# Facee.net
KiCad netlist of a schematic drawn in EAGLE
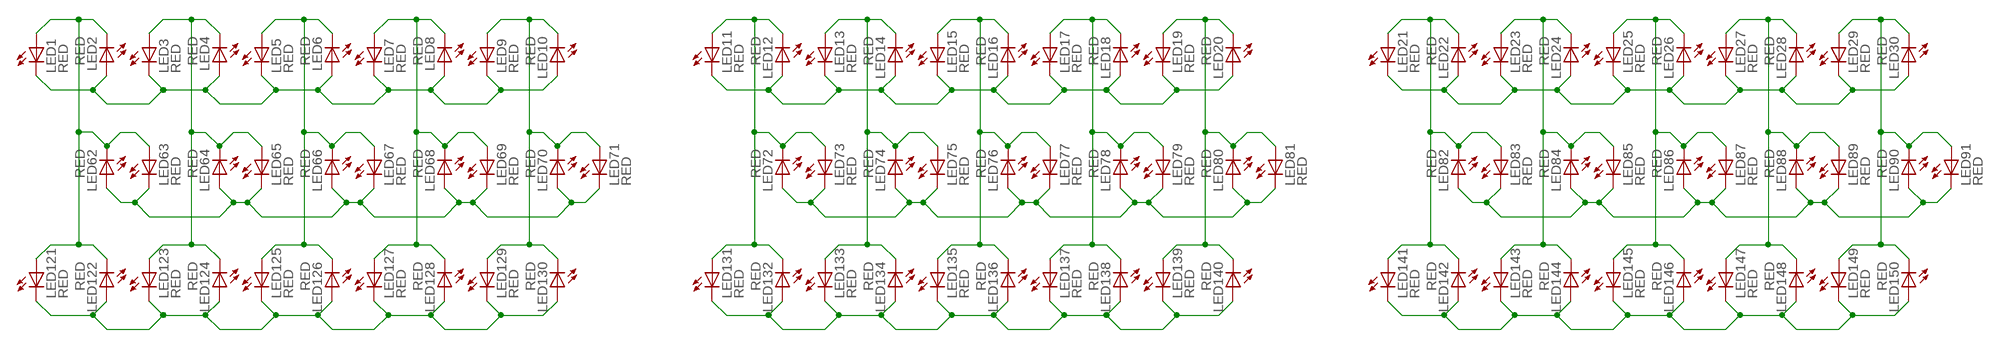
[diagram p0: schematic, sheet 1, part 1 of 2]
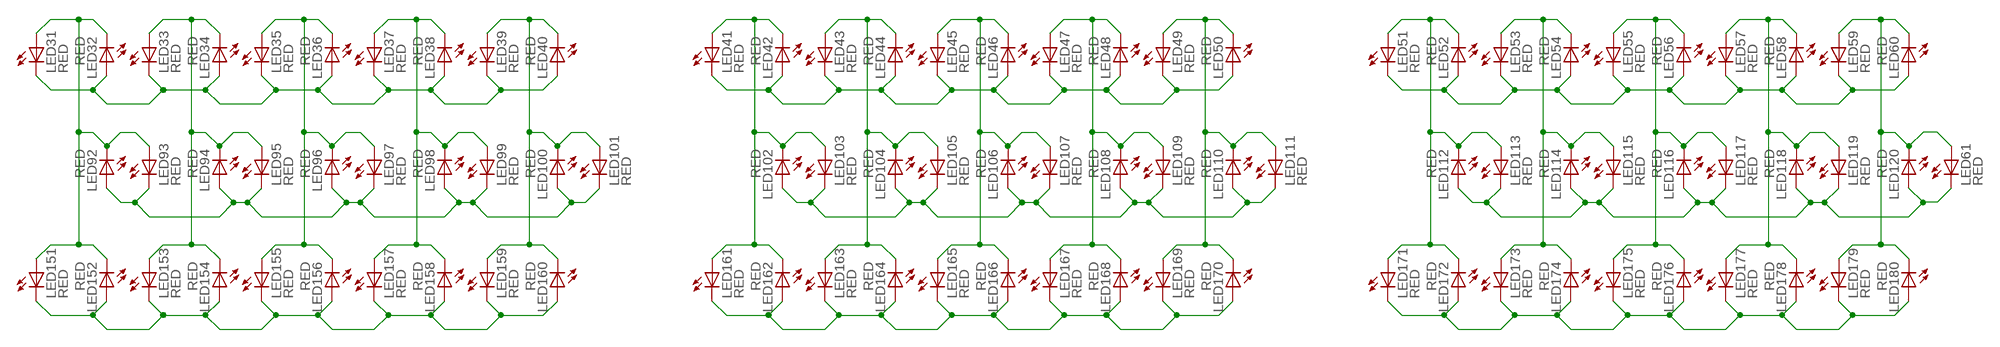
[diagram p1: schematic, sheet 1, part 2 of 2]

(export (version "E")
  (design (tool "Eeschema 10.0.6"))
  (components
    (comp (ref "LED1")
      (value "RED")
      (footprint "eagle-import:LED-0603")
      (libsource (lib "eagle-import") (part "LED0603"))
    )
    (comp (ref "LED2")
      (value "RED")
      (footprint "eagle-import:LED-0603")
      (libsource (lib "eagle-import") (part "LED0603"))
    )
    (comp (ref "LED3")
      (value "RED")
      (footprint "eagle-import:LED-0603")
      (libsource (lib "eagle-import") (part "LED0603"))
    )
    (comp (ref "LED4")
      (value "RED")
      (footprint "eagle-import:LED-0603")
      (libsource (lib "eagle-import") (part "LED0603"))
    )
    (comp (ref "LED5")
      (value "RED")
      (footprint "eagle-import:LED-0603")
      (libsource (lib "eagle-import") (part "LED0603"))
    )
    (comp (ref "LED6")
      (value "RED")
      (footprint "eagle-import:LED-0603")
      (libsource (lib "eagle-import") (part "LED0603"))
    )
    (comp (ref "LED7")
      (value "RED")
      (footprint "eagle-import:LED-0603")
      (libsource (lib "eagle-import") (part "LED0603"))
    )
    (comp (ref "LED8")
      (value "RED")
      (footprint "eagle-import:LED-0603")
      (libsource (lib "eagle-import") (part "LED0603"))
    )
    (comp (ref "LED9")
      (value "RED")
      (footprint "eagle-import:LED-0603")
      (libsource (lib "eagle-import") (part "LED0603"))
    )
    (comp (ref "LED10")
      (value "RED")
      (footprint "eagle-import:LED-0603")
      (libsource (lib "eagle-import") (part "LED0603"))
    )
    (comp (ref "LED11")
      (value "RED")
      (footprint "eagle-import:LED-0603")
      (libsource (lib "eagle-import") (part "LED0603"))
    )
    (comp (ref "LED12")
      (value "RED")
      (footprint "eagle-import:LED-0603")
      (libsource (lib "eagle-import") (part "LED0603"))
    )
    (comp (ref "LED13")
      (value "RED")
      (footprint "eagle-import:LED-0603")
      (libsource (lib "eagle-import") (part "LED0603"))
    )
    (comp (ref "LED14")
      (value "RED")
      (footprint "eagle-import:LED-0603")
      (libsource (lib "eagle-import") (part "LED0603"))
    )
    (comp (ref "LED15")
      (value "RED")
      (footprint "eagle-import:LED-0603")
      (libsource (lib "eagle-import") (part "LED0603"))
    )
    (comp (ref "LED16")
      (value "RED")
      (footprint "eagle-import:LED-0603")
      (libsource (lib "eagle-import") (part "LED0603"))
    )
    (comp (ref "LED17")
      (value "RED")
      (footprint "eagle-import:LED-0603")
      (libsource (lib "eagle-import") (part "LED0603"))
    )
    (comp (ref "LED18")
      (value "RED")
      (footprint "eagle-import:LED-0603")
      (libsource (lib "eagle-import") (part "LED0603"))
    )
    (comp (ref "LED19")
      (value "RED")
      (footprint "eagle-import:LED-0603")
      (libsource (lib "eagle-import") (part "LED0603"))
    )
    (comp (ref "LED20")
      (value "RED")
      (footprint "eagle-import:LED-0603")
      (libsource (lib "eagle-import") (part "LED0603"))
    )
    (comp (ref "LED21")
      (value "RED")
      (footprint "eagle-import:LED-0603")
      (libsource (lib "eagle-import") (part "LED0603"))
    )
    (comp (ref "LED22")
      (value "RED")
      (footprint "eagle-import:LED-0603")
      (libsource (lib "eagle-import") (part "LED0603"))
    )
    (comp (ref "LED23")
      (value "RED")
      (footprint "eagle-import:LED-0603")
      (libsource (lib "eagle-import") (part "LED0603"))
    )
    (comp (ref "LED24")
      (value "RED")
      (footprint "eagle-import:LED-0603")
      (libsource (lib "eagle-import") (part "LED0603"))
    )
    (comp (ref "LED25")
      (value "RED")
      (footprint "eagle-import:LED-0603")
      (libsource (lib "eagle-import") (part "LED0603"))
    )
    (comp (ref "LED26")
      (value "RED")
      (footprint "eagle-import:LED-0603")
      (libsource (lib "eagle-import") (part "LED0603"))
    )
    (comp (ref "LED27")
      (value "RED")
      (footprint "eagle-import:LED-0603")
      (libsource (lib "eagle-import") (part "LED0603"))
    )
    (comp (ref "LED28")
      (value "RED")
      (footprint "eagle-import:LED-0603")
      (libsource (lib "eagle-import") (part "LED0603"))
    )
    (comp (ref "LED29")
      (value "RED")
      (footprint "eagle-import:LED-0603")
      (libsource (lib "eagle-import") (part "LED0603"))
    )
    (comp (ref "LED30")
      (value "RED")
      (footprint "eagle-import:LED-0603")
      (libsource (lib "eagle-import") (part "LED0603"))
    )
    (comp (ref "LED31")
      (value "RED")
      (footprint "eagle-import:LED-0603")
      (libsource (lib "eagle-import") (part "LED0603"))
    )
    (comp (ref "LED32")
      (value "RED")
      (footprint "eagle-import:LED-0603")
      (libsource (lib "eagle-import") (part "LED0603"))
    )
    (comp (ref "LED33")
      (value "RED")
      (footprint "eagle-import:LED-0603")
      (libsource (lib "eagle-import") (part "LED0603"))
    )
    (comp (ref "LED34")
      (value "RED")
      (footprint "eagle-import:LED-0603")
      (libsource (lib "eagle-import") (part "LED0603"))
    )
    (comp (ref "LED35")
      (value "RED")
      (footprint "eagle-import:LED-0603")
      (libsource (lib "eagle-import") (part "LED0603"))
    )
    (comp (ref "LED36")
      (value "RED")
      (footprint "eagle-import:LED-0603")
      (libsource (lib "eagle-import") (part "LED0603"))
    )
    (comp (ref "LED37")
      (value "RED")
      (footprint "eagle-import:LED-0603")
      (libsource (lib "eagle-import") (part "LED0603"))
    )
    (comp (ref "LED38")
      (value "RED")
      (footprint "eagle-import:LED-0603")
      (libsource (lib "eagle-import") (part "LED0603"))
    )
    (comp (ref "LED39")
      (value "RED")
      (footprint "eagle-import:LED-0603")
      (libsource (lib "eagle-import") (part "LED0603"))
    )
    (comp (ref "LED40")
      (value "RED")
      (footprint "eagle-import:LED-0603")
      (libsource (lib "eagle-import") (part "LED0603"))
    )
    (comp (ref "LED41")
      (value "RED")
      (footprint "eagle-import:LED-0603")
      (libsource (lib "eagle-import") (part "LED0603"))
    )
    (comp (ref "LED42")
      (value "RED")
      (footprint "eagle-import:LED-0603")
      (libsource (lib "eagle-import") (part "LED0603"))
    )
    (comp (ref "LED43")
      (value "RED")
      (footprint "eagle-import:LED-0603")
      (libsource (lib "eagle-import") (part "LED0603"))
    )
    (comp (ref "LED44")
      (value "RED")
      (footprint "eagle-import:LED-0603")
      (libsource (lib "eagle-import") (part "LED0603"))
    )
    (comp (ref "LED45")
      (value "RED")
      (footprint "eagle-import:LED-0603")
      (libsource (lib "eagle-import") (part "LED0603"))
    )
    (comp (ref "LED46")
      (value "RED")
      (footprint "eagle-import:LED-0603")
      (libsource (lib "eagle-import") (part "LED0603"))
    )
    (comp (ref "LED47")
      (value "RED")
      (footprint "eagle-import:LED-0603")
      (libsource (lib "eagle-import") (part "LED0603"))
    )
    (comp (ref "LED48")
      (value "RED")
      (footprint "eagle-import:LED-0603")
      (libsource (lib "eagle-import") (part "LED0603"))
    )
    (comp (ref "LED49")
      (value "RED")
      (footprint "eagle-import:LED-0603")
      (libsource (lib "eagle-import") (part "LED0603"))
    )
    (comp (ref "LED50")
      (value "RED")
      (footprint "eagle-import:LED-0603")
      (libsource (lib "eagle-import") (part "LED0603"))
    )
    (comp (ref "LED51")
      (value "RED")
      (footprint "eagle-import:LED-0603")
      (libsource (lib "eagle-import") (part "LED0603"))
    )
    (comp (ref "LED52")
      (value "RED")
      (footprint "eagle-import:LED-0603")
      (libsource (lib "eagle-import") (part "LED0603"))
    )
    (comp (ref "LED53")
      (value "RED")
      (footprint "eagle-import:LED-0603")
      (libsource (lib "eagle-import") (part "LED0603"))
    )
    (comp (ref "LED54")
      (value "RED")
      (footprint "eagle-import:LED-0603")
      (libsource (lib "eagle-import") (part "LED0603"))
    )
    (comp (ref "LED55")
      (value "RED")
      (footprint "eagle-import:LED-0603")
      (libsource (lib "eagle-import") (part "LED0603"))
    )
    (comp (ref "LED56")
      (value "RED")
      (footprint "eagle-import:LED-0603")
      (libsource (lib "eagle-import") (part "LED0603"))
    )
    (comp (ref "LED57")
      (value "RED")
      (footprint "eagle-import:LED-0603")
      (libsource (lib "eagle-import") (part "LED0603"))
    )
    (comp (ref "LED58")
      (value "RED")
      (footprint "eagle-import:LED-0603")
      (libsource (lib "eagle-import") (part "LED0603"))
    )
    (comp (ref "LED59")
      (value "RED")
      (footprint "eagle-import:LED-0603")
      (libsource (lib "eagle-import") (part "LED0603"))
    )
    (comp (ref "LED60")
      (value "RED")
      (footprint "eagle-import:LED-0603")
      (libsource (lib "eagle-import") (part "LED0603"))
    )
    (comp (ref "LED61")
      (value "RED")
      (footprint "eagle-import:LED-0603")
      (libsource (lib "eagle-import") (part "LED0603"))
    )
    (comp (ref "LED62")
      (value "RED")
      (footprint "eagle-import:LED-0603")
      (libsource (lib "eagle-import") (part "LED0603"))
    )
    (comp (ref "LED63")
      (value "RED")
      (footprint "eagle-import:LED-0603")
      (libsource (lib "eagle-import") (part "LED0603"))
    )
    (comp (ref "LED64")
      (value "RED")
      (footprint "eagle-import:LED-0603")
      (libsource (lib "eagle-import") (part "LED0603"))
    )
    (comp (ref "LED65")
      (value "RED")
      (footprint "eagle-import:LED-0603")
      (libsource (lib "eagle-import") (part "LED0603"))
    )
    (comp (ref "LED66")
      (value "RED")
      (footprint "eagle-import:LED-0603")
      (libsource (lib "eagle-import") (part "LED0603"))
    )
    (comp (ref "LED67")
      (value "RED")
      (footprint "eagle-import:LED-0603")
      (libsource (lib "eagle-import") (part "LED0603"))
    )
    (comp (ref "LED68")
      (value "RED")
      (footprint "eagle-import:LED-0603")
      (libsource (lib "eagle-import") (part "LED0603"))
    )
    (comp (ref "LED69")
      (value "RED")
      (footprint "eagle-import:LED-0603")
      (libsource (lib "eagle-import") (part "LED0603"))
    )
    (comp (ref "LED70")
      (value "RED")
      (footprint "eagle-import:LED-0603")
      (libsource (lib "eagle-import") (part "LED0603"))
    )
    (comp (ref "LED71")
      (value "RED")
      (footprint "eagle-import:LED-0603")
      (libsource (lib "eagle-import") (part "LED0603"))
    )
    (comp (ref "LED72")
      (value "RED")
      (footprint "eagle-import:LED-0603")
      (libsource (lib "eagle-import") (part "LED0603"))
    )
    (comp (ref "LED73")
      (value "RED")
      (footprint "eagle-import:LED-0603")
      (libsource (lib "eagle-import") (part "LED0603"))
    )
    (comp (ref "LED74")
      (value "RED")
      (footprint "eagle-import:LED-0603")
      (libsource (lib "eagle-import") (part "LED0603"))
    )
    (comp (ref "LED75")
      (value "RED")
      (footprint "eagle-import:LED-0603")
      (libsource (lib "eagle-import") (part "LED0603"))
    )
    (comp (ref "LED76")
      (value "RED")
      (footprint "eagle-import:LED-0603")
      (libsource (lib "eagle-import") (part "LED0603"))
    )
    (comp (ref "LED77")
      (value "RED")
      (footprint "eagle-import:LED-0603")
      (libsource (lib "eagle-import") (part "LED0603"))
    )
    (comp (ref "LED78")
      (value "RED")
      (footprint "eagle-import:LED-0603")
      (libsource (lib "eagle-import") (part "LED0603"))
    )
    (comp (ref "LED79")
      (value "RED")
      (footprint "eagle-import:LED-0603")
      (libsource (lib "eagle-import") (part "LED0603"))
    )
    (comp (ref "LED80")
      (value "RED")
      (footprint "eagle-import:LED-0603")
      (libsource (lib "eagle-import") (part "LED0603"))
    )
    (comp (ref "LED81")
      (value "RED")
      (footprint "eagle-import:LED-0603")
      (libsource (lib "eagle-import") (part "LED0603"))
    )
    (comp (ref "LED82")
      (value "RED")
      (footprint "eagle-import:LED-0603")
      (libsource (lib "eagle-import") (part "LED0603"))
    )
    (comp (ref "LED83")
      (value "RED")
      (footprint "eagle-import:LED-0603")
      (libsource (lib "eagle-import") (part "LED0603"))
    )
    (comp (ref "LED84")
      (value "RED")
      (footprint "eagle-import:LED-0603")
      (libsource (lib "eagle-import") (part "LED0603"))
    )
    (comp (ref "LED85")
      (value "RED")
      (footprint "eagle-import:LED-0603")
      (libsource (lib "eagle-import") (part "LED0603"))
    )
    (comp (ref "LED86")
      (value "RED")
      (footprint "eagle-import:LED-0603")
      (libsource (lib "eagle-import") (part "LED0603"))
    )
    (comp (ref "LED87")
      (value "RED")
      (footprint "eagle-import:LED-0603")
      (libsource (lib "eagle-import") (part "LED0603"))
    )
    (comp (ref "LED88")
      (value "RED")
      (footprint "eagle-import:LED-0603")
      (libsource (lib "eagle-import") (part "LED0603"))
    )
    (comp (ref "LED89")
      (value "RED")
      (footprint "eagle-import:LED-0603")
      (libsource (lib "eagle-import") (part "LED0603"))
    )
    (comp (ref "LED90")
      (value "RED")
      (footprint "eagle-import:LED-0603")
      (libsource (lib "eagle-import") (part "LED0603"))
    )
    (comp (ref "LED91")
      (value "RED")
      (footprint "eagle-import:LED-0603")
      (libsource (lib "eagle-import") (part "LED0603"))
    )
    (comp (ref "LED92")
      (value "RED")
      (footprint "eagle-import:LED-0603")
      (libsource (lib "eagle-import") (part "LED0603"))
    )
    (comp (ref "LED93")
      (value "RED")
      (footprint "eagle-import:LED-0603")
      (libsource (lib "eagle-import") (part "LED0603"))
    )
    (comp (ref "LED94")
      (value "RED")
      (footprint "eagle-import:LED-0603")
      (libsource (lib "eagle-import") (part "LED0603"))
    )
    (comp (ref "LED95")
      (value "RED")
      (footprint "eagle-import:LED-0603")
      (libsource (lib "eagle-import") (part "LED0603"))
    )
    (comp (ref "LED96")
      (value "RED")
      (footprint "eagle-import:LED-0603")
      (libsource (lib "eagle-import") (part "LED0603"))
    )
    (comp (ref "LED97")
      (value "RED")
      (footprint "eagle-import:LED-0603")
      (libsource (lib "eagle-import") (part "LED0603"))
    )
    (comp (ref "LED98")
      (value "RED")
      (footprint "eagle-import:LED-0603")
      (libsource (lib "eagle-import") (part "LED0603"))
    )
    (comp (ref "LED99")
      (value "RED")
      (footprint "eagle-import:LED-0603")
      (libsource (lib "eagle-import") (part "LED0603"))
    )
    (comp (ref "LED100")
      (value "RED")
      (footprint "eagle-import:LED-0603")
      (libsource (lib "eagle-import") (part "LED0603"))
    )
    (comp (ref "LED101")
      (value "RED")
      (footprint "eagle-import:LED-0603")
      (libsource (lib "eagle-import") (part "LED0603"))
    )
    (comp (ref "LED102")
      (value "RED")
      (footprint "eagle-import:LED-0603")
      (libsource (lib "eagle-import") (part "LED0603"))
    )
    (comp (ref "LED103")
      (value "RED")
      (footprint "eagle-import:LED-0603")
      (libsource (lib "eagle-import") (part "LED0603"))
    )
    (comp (ref "LED104")
      (value "RED")
      (footprint "eagle-import:LED-0603")
      (libsource (lib "eagle-import") (part "LED0603"))
    )
    (comp (ref "LED105")
      (value "RED")
      (footprint "eagle-import:LED-0603")
      (libsource (lib "eagle-import") (part "LED0603"))
    )
    (comp (ref "LED106")
      (value "RED")
      (footprint "eagle-import:LED-0603")
      (libsource (lib "eagle-import") (part "LED0603"))
    )
    (comp (ref "LED107")
      (value "RED")
      (footprint "eagle-import:LED-0603")
      (libsource (lib "eagle-import") (part "LED0603"))
    )
    (comp (ref "LED108")
      (value "RED")
      (footprint "eagle-import:LED-0603")
      (libsource (lib "eagle-import") (part "LED0603"))
    )
    (comp (ref "LED109")
      (value "RED")
      (footprint "eagle-import:LED-0603")
      (libsource (lib "eagle-import") (part "LED0603"))
    )
    (comp (ref "LED110")
      (value "RED")
      (footprint "eagle-import:LED-0603")
      (libsource (lib "eagle-import") (part "LED0603"))
    )
    (comp (ref "LED111")
      (value "RED")
      (footprint "eagle-import:LED-0603")
      (libsource (lib "eagle-import") (part "LED0603"))
    )
    (comp (ref "LED112")
      (value "RED")
      (footprint "eagle-import:LED-0603")
      (libsource (lib "eagle-import") (part "LED0603"))
    )
    (comp (ref "LED113")
      (value "RED")
      (footprint "eagle-import:LED-0603")
      (libsource (lib "eagle-import") (part "LED0603"))
    )
    (comp (ref "LED114")
      (value "RED")
      (footprint "eagle-import:LED-0603")
      (libsource (lib "eagle-import") (part "LED0603"))
    )
    (comp (ref "LED115")
      (value "RED")
      (footprint "eagle-import:LED-0603")
      (libsource (lib "eagle-import") (part "LED0603"))
    )
    (comp (ref "LED116")
      (value "RED")
      (footprint "eagle-import:LED-0603")
      (libsource (lib "eagle-import") (part "LED0603"))
    )
    (comp (ref "LED117")
      (value "RED")
      (footprint "eagle-import:LED-0603")
      (libsource (lib "eagle-import") (part "LED0603"))
    )
    (comp (ref "LED118")
      (value "RED")
      (footprint "eagle-import:LED-0603")
      (libsource (lib "eagle-import") (part "LED0603"))
    )
    (comp (ref "LED119")
      (value "RED")
      (footprint "eagle-import:LED-0603")
      (libsource (lib "eagle-import") (part "LED0603"))
    )
    (comp (ref "LED120")
      (value "RED")
      (footprint "eagle-import:LED-0603")
      (libsource (lib "eagle-import") (part "LED0603"))
    )
    (comp (ref "LED121")
      (value "RED")
      (footprint "eagle-import:LED-0603")
      (libsource (lib "eagle-import") (part "LED0603"))
    )
    (comp (ref "LED122")
      (value "RED")
      (footprint "eagle-import:LED-0603")
      (libsource (lib "eagle-import") (part "LED0603"))
    )
    (comp (ref "LED123")
      (value "RED")
      (footprint "eagle-import:LED-0603")
      (libsource (lib "eagle-import") (part "LED0603"))
    )
    (comp (ref "LED124")
      (value "RED")
      (footprint "eagle-import:LED-0603")
      (libsource (lib "eagle-import") (part "LED0603"))
    )
    (comp (ref "LED125")
      (value "RED")
      (footprint "eagle-import:LED-0603")
      (libsource (lib "eagle-import") (part "LED0603"))
    )
    (comp (ref "LED126")
      (value "RED")
      (footprint "eagle-import:LED-0603")
      (libsource (lib "eagle-import") (part "LED0603"))
    )
    (comp (ref "LED127")
      (value "RED")
      (footprint "eagle-import:LED-0603")
      (libsource (lib "eagle-import") (part "LED0603"))
    )
    (comp (ref "LED128")
      (value "RED")
      (footprint "eagle-import:LED-0603")
      (libsource (lib "eagle-import") (part "LED0603"))
    )
    (comp (ref "LED129")
      (value "RED")
      (footprint "eagle-import:LED-0603")
      (libsource (lib "eagle-import") (part "LED0603"))
    )
    (comp (ref "LED130")
      (value "RED")
      (footprint "eagle-import:LED-0603")
      (libsource (lib "eagle-import") (part "LED0603"))
    )
    (comp (ref "LED131")
      (value "RED")
      (footprint "eagle-import:LED-0603")
      (libsource (lib "eagle-import") (part "LED0603"))
    )
    (comp (ref "LED132")
      (value "RED")
      (footprint "eagle-import:LED-0603")
      (libsource (lib "eagle-import") (part "LED0603"))
    )
    (comp (ref "LED133")
      (value "RED")
      (footprint "eagle-import:LED-0603")
      (libsource (lib "eagle-import") (part "LED0603"))
    )
    (comp (ref "LED134")
      (value "RED")
      (footprint "eagle-import:LED-0603")
      (libsource (lib "eagle-import") (part "LED0603"))
    )
    (comp (ref "LED135")
      (value "RED")
      (footprint "eagle-import:LED-0603")
      (libsource (lib "eagle-import") (part "LED0603"))
    )
    (comp (ref "LED136")
      (value "RED")
      (footprint "eagle-import:LED-0603")
      (libsource (lib "eagle-import") (part "LED0603"))
    )
    (comp (ref "LED137")
      (value "RED")
      (footprint "eagle-import:LED-0603")
      (libsource (lib "eagle-import") (part "LED0603"))
    )
    (comp (ref "LED138")
      (value "RED")
      (footprint "eagle-import:LED-0603")
      (libsource (lib "eagle-import") (part "LED0603"))
    )
    (comp (ref "LED139")
      (value "RED")
      (footprint "eagle-import:LED-0603")
      (libsource (lib "eagle-import") (part "LED0603"))
    )
    (comp (ref "LED140")
      (value "RED")
      (footprint "eagle-import:LED-0603")
      (libsource (lib "eagle-import") (part "LED0603"))
    )
    (comp (ref "LED141")
      (value "RED")
      (footprint "eagle-import:LED-0603")
      (libsource (lib "eagle-import") (part "LED0603"))
    )
    (comp (ref "LED142")
      (value "RED")
      (footprint "eagle-import:LED-0603")
      (libsource (lib "eagle-import") (part "LED0603"))
    )
    (comp (ref "LED143")
      (value "RED")
      (footprint "eagle-import:LED-0603")
      (libsource (lib "eagle-import") (part "LED0603"))
    )
    (comp (ref "LED144")
      (value "RED")
      (footprint "eagle-import:LED-0603")
      (libsource (lib "eagle-import") (part "LED0603"))
    )
    (comp (ref "LED145")
      (value "RED")
      (footprint "eagle-import:LED-0603")
      (libsource (lib "eagle-import") (part "LED0603"))
    )
    (comp (ref "LED146")
      (value "RED")
      (footprint "eagle-import:LED-0603")
      (libsource (lib "eagle-import") (part "LED0603"))
    )
    (comp (ref "LED147")
      (value "RED")
      (footprint "eagle-import:LED-0603")
      (libsource (lib "eagle-import") (part "LED0603"))
    )
    (comp (ref "LED148")
      (value "RED")
      (footprint "eagle-import:LED-0603")
      (libsource (lib "eagle-import") (part "LED0603"))
    )
    (comp (ref "LED149")
      (value "RED")
      (footprint "eagle-import:LED-0603")
      (libsource (lib "eagle-import") (part "LED0603"))
    )
    (comp (ref "LED150")
      (value "RED")
      (footprint "eagle-import:LED-0603")
      (libsource (lib "eagle-import") (part "LED0603"))
    )
    (comp (ref "LED151")
      (value "RED")
      (footprint "eagle-import:LED-0603")
      (libsource (lib "eagle-import") (part "LED0603"))
    )
    (comp (ref "LED152")
      (value "RED")
      (footprint "eagle-import:LED-0603")
      (libsource (lib "eagle-import") (part "LED0603"))
    )
    (comp (ref "LED153")
      (value "RED")
      (footprint "eagle-import:LED-0603")
      (libsource (lib "eagle-import") (part "LED0603"))
    )
    (comp (ref "LED154")
      (value "RED")
      (footprint "eagle-import:LED-0603")
      (libsource (lib "eagle-import") (part "LED0603"))
    )
    (comp (ref "LED155")
      (value "RED")
      (footprint "eagle-import:LED-0603")
      (libsource (lib "eagle-import") (part "LED0603"))
    )
    (comp (ref "LED156")
      (value "RED")
      (footprint "eagle-import:LED-0603")
      (libsource (lib "eagle-import") (part "LED0603"))
    )
    (comp (ref "LED157")
      (value "RED")
      (footprint "eagle-import:LED-0603")
      (libsource (lib "eagle-import") (part "LED0603"))
    )
    (comp (ref "LED158")
      (value "RED")
      (footprint "eagle-import:LED-0603")
      (libsource (lib "eagle-import") (part "LED0603"))
    )
    (comp (ref "LED159")
      (value "RED")
      (footprint "eagle-import:LED-0603")
      (libsource (lib "eagle-import") (part "LED0603"))
    )
    (comp (ref "LED160")
      (value "RED")
      (footprint "eagle-import:LED-0603")
      (libsource (lib "eagle-import") (part "LED0603"))
    )
    (comp (ref "LED161")
      (value "RED")
      (footprint "eagle-import:LED-0603")
      (libsource (lib "eagle-import") (part "LED0603"))
    )
    (comp (ref "LED162")
      (value "RED")
      (footprint "eagle-import:LED-0603")
      (libsource (lib "eagle-import") (part "LED0603"))
    )
    (comp (ref "LED163")
      (value "RED")
      (footprint "eagle-import:LED-0603")
      (libsource (lib "eagle-import") (part "LED0603"))
    )
    (comp (ref "LED164")
      (value "RED")
      (footprint "eagle-import:LED-0603")
      (libsource (lib "eagle-import") (part "LED0603"))
    )
    (comp (ref "LED165")
      (value "RED")
      (footprint "eagle-import:LED-0603")
      (libsource (lib "eagle-import") (part "LED0603"))
    )
    (comp (ref "LED166")
      (value "RED")
      (footprint "eagle-import:LED-0603")
      (libsource (lib "eagle-import") (part "LED0603"))
    )
    (comp (ref "LED167")
      (value "RED")
      (footprint "eagle-import:LED-0603")
      (libsource (lib "eagle-import") (part "LED0603"))
    )
    (comp (ref "LED168")
      (value "RED")
      (footprint "eagle-import:LED-0603")
      (libsource (lib "eagle-import") (part "LED0603"))
    )
    (comp (ref "LED169")
      (value "RED")
      (footprint "eagle-import:LED-0603")
      (libsource (lib "eagle-import") (part "LED0603"))
    )
    (comp (ref "LED170")
      (value "RED")
      (footprint "eagle-import:LED-0603")
      (libsource (lib "eagle-import") (part "LED0603"))
    )
    (comp (ref "LED171")
      (value "RED")
      (footprint "eagle-import:LED-0603")
      (libsource (lib "eagle-import") (part "LED0603"))
    )
    (comp (ref "LED172")
      (value "RED")
      (footprint "eagle-import:LED-0603")
      (libsource (lib "eagle-import") (part "LED0603"))
    )
    (comp (ref "LED173")
      (value "RED")
      (footprint "eagle-import:LED-0603")
      (libsource (lib "eagle-import") (part "LED0603"))
    )
    (comp (ref "LED174")
      (value "RED")
      (footprint "eagle-import:LED-0603")
      (libsource (lib "eagle-import") (part "LED0603"))
    )
    (comp (ref "LED175")
      (value "RED")
      (footprint "eagle-import:LED-0603")
      (libsource (lib "eagle-import") (part "LED0603"))
    )
    (comp (ref "LED176")
      (value "RED")
      (footprint "eagle-import:LED-0603")
      (libsource (lib "eagle-import") (part "LED0603"))
    )
    (comp (ref "LED177")
      (value "RED")
      (footprint "eagle-import:LED-0603")
      (libsource (lib "eagle-import") (part "LED0603"))
    )
    (comp (ref "LED178")
      (value "RED")
      (footprint "eagle-import:LED-0603")
      (libsource (lib "eagle-import") (part "LED0603"))
    )
    (comp (ref "LED179")
      (value "RED")
      (footprint "eagle-import:LED-0603")
      (libsource (lib "eagle-import") (part "LED0603"))
    )
    (comp (ref "LED180")
      (value "RED")
      (footprint "eagle-import:LED-0603")
      (libsource (lib "eagle-import") (part "LED0603"))
    )
  )
  (nets
    (net (code "1") (name "/1") (class "Default")
      (node (ref "LED1") (pin "C") (pinfunction "C_C") (pintype "passive"))
      (node (ref "LED10") (pin "A") (pinfunction "A_A") (pintype "passive"))
      (node (ref "LED11") (pin "C") (pinfunction "C_C") (pintype "passive"))
      (node (ref "LED12") (pin "A") (pinfunction "A_A") (pintype "passive"))
      (node (ref "LED13") (pin "C") (pinfunction "C_C") (pintype "passive"))
      (node (ref "LED14") (pin "A") (pinfunction "A_A") (pintype "passive"))
      (node (ref "LED141") (pin "A") (pinfunction "A_A") (pintype "passive"))
      (node (ref "LED142") (pin "C") (pinfunction "C_C") (pintype "passive"))
      (node (ref "LED15") (pin "C") (pinfunction "C_C") (pintype "passive"))
      (node (ref "LED16") (pin "A") (pinfunction "A_A") (pintype "passive"))
      (node (ref "LED17") (pin "C") (pinfunction "C_C") (pintype "passive"))
      (node (ref "LED18") (pin "A") (pinfunction "A_A") (pintype "passive"))
      (node (ref "LED19") (pin "C") (pinfunction "C_C") (pintype "passive"))
      (node (ref "LED2") (pin "A") (pinfunction "A_A") (pintype "passive"))
      (node (ref "LED20") (pin "A") (pinfunction "A_A") (pintype "passive"))
      (node (ref "LED21") (pin "A") (pinfunction "A_A") (pintype "passive"))
      (node (ref "LED22") (pin "C") (pinfunction "C_C") (pintype "passive"))
      (node (ref "LED3") (pin "C") (pinfunction "C_C") (pintype "passive"))
      (node (ref "LED4") (pin "A") (pinfunction "A_A") (pintype "passive"))
      (node (ref "LED5") (pin "C") (pinfunction "C_C") (pintype "passive"))
      (node (ref "LED6") (pin "A") (pinfunction "A_A") (pintype "passive"))
      (node (ref "LED7") (pin "C") (pinfunction "C_C") (pintype "passive"))
      (node (ref "LED8") (pin "A") (pinfunction "A_A") (pintype "passive"))
      (node (ref "LED82") (pin "C") (pinfunction "C_C") (pintype "passive"))
      (node (ref "LED83") (pin "A") (pinfunction "A_A") (pintype "passive"))
      (node (ref "LED9") (pin "C") (pinfunction "C_C") (pintype "passive"))
    )
    (net (code "2") (name "/2") (class "Default")
      (node (ref "LED143") (pin "A") (pinfunction "A_A") (pintype "passive"))
      (node (ref "LED144") (pin "C") (pinfunction "C_C") (pintype "passive"))
      (node (ref "LED23") (pin "A") (pinfunction "A_A") (pintype "passive"))
      (node (ref "LED24") (pin "C") (pinfunction "C_C") (pintype "passive"))
      (node (ref "LED62") (pin "A") (pinfunction "A_A") (pintype "passive"))
      (node (ref "LED63") (pin "C") (pinfunction "C_C") (pintype "passive"))
      (node (ref "LED64") (pin "A") (pinfunction "A_A") (pintype "passive"))
      (node (ref "LED65") (pin "C") (pinfunction "C_C") (pintype "passive"))
      (node (ref "LED66") (pin "A") (pinfunction "A_A") (pintype "passive"))
      (node (ref "LED67") (pin "C") (pinfunction "C_C") (pintype "passive"))
      (node (ref "LED68") (pin "A") (pinfunction "A_A") (pintype "passive"))
      (node (ref "LED69") (pin "C") (pinfunction "C_C") (pintype "passive"))
      (node (ref "LED70") (pin "A") (pinfunction "A_A") (pintype "passive"))
      (node (ref "LED71") (pin "C") (pinfunction "C_C") (pintype "passive"))
      (node (ref "LED72") (pin "A") (pinfunction "A_A") (pintype "passive"))
      (node (ref "LED73") (pin "C") (pinfunction "C_C") (pintype "passive"))
      (node (ref "LED74") (pin "A") (pinfunction "A_A") (pintype "passive"))
      (node (ref "LED75") (pin "C") (pinfunction "C_C") (pintype "passive"))
      (node (ref "LED76") (pin "A") (pinfunction "A_A") (pintype "passive"))
      (node (ref "LED77") (pin "C") (pinfunction "C_C") (pintype "passive"))
      (node (ref "LED78") (pin "A") (pinfunction "A_A") (pintype "passive"))
      (node (ref "LED79") (pin "C") (pinfunction "C_C") (pintype "passive"))
      (node (ref "LED80") (pin "A") (pinfunction "A_A") (pintype "passive"))
      (node (ref "LED81") (pin "C") (pinfunction "C_C") (pintype "passive"))
      (node (ref "LED84") (pin "C") (pinfunction "C_C") (pintype "passive"))
      (node (ref "LED85") (pin "A") (pinfunction "A_A") (pintype "passive"))
    )
    (net (code "3") (name "/3") (class "Default")
      (node (ref "LED121") (pin "C") (pinfunction "C_C") (pintype "passive"))
      (node (ref "LED122") (pin "A") (pinfunction "A_A") (pintype "passive"))
      (node (ref "LED123") (pin "C") (pinfunction "C_C") (pintype "passive"))
      (node (ref "LED124") (pin "A") (pinfunction "A_A") (pintype "passive"))
      (node (ref "LED125") (pin "C") (pinfunction "C_C") (pintype "passive"))
      (node (ref "LED126") (pin "A") (pinfunction "A_A") (pintype "passive"))
      (node (ref "LED127") (pin "C") (pinfunction "C_C") (pintype "passive"))
      (node (ref "LED128") (pin "A") (pinfunction "A_A") (pintype "passive"))
      (node (ref "LED129") (pin "C") (pinfunction "C_C") (pintype "passive"))
      (node (ref "LED130") (pin "A") (pinfunction "A_A") (pintype "passive"))
      (node (ref "LED131") (pin "C") (pinfunction "C_C") (pintype "passive"))
      (node (ref "LED132") (pin "A") (pinfunction "A_A") (pintype "passive"))
      (node (ref "LED133") (pin "C") (pinfunction "C_C") (pintype "passive"))
      (node (ref "LED134") (pin "A") (pinfunction "A_A") (pintype "passive"))
      (node (ref "LED135") (pin "C") (pinfunction "C_C") (pintype "passive"))
      (node (ref "LED136") (pin "A") (pinfunction "A_A") (pintype "passive"))
      (node (ref "LED137") (pin "C") (pinfunction "C_C") (pintype "passive"))
      (node (ref "LED138") (pin "A") (pinfunction "A_A") (pintype "passive"))
      (node (ref "LED139") (pin "C") (pinfunction "C_C") (pintype "passive"))
      (node (ref "LED140") (pin "A") (pinfunction "A_A") (pintype "passive"))
      (node (ref "LED145") (pin "A") (pinfunction "A_A") (pintype "passive"))
      (node (ref "LED146") (pin "C") (pinfunction "C_C") (pintype "passive"))
      (node (ref "LED25") (pin "A") (pinfunction "A_A") (pintype "passive"))
      (node (ref "LED26") (pin "C") (pinfunction "C_C") (pintype "passive"))
      (node (ref "LED86") (pin "C") (pinfunction "C_C") (pintype "passive"))
      (node (ref "LED87") (pin "A") (pinfunction "A_A") (pintype "passive"))
    )
    (net (code "4") (name "/4") (class "Default")
      (node (ref "LED1") (pin "A") (pinfunction "A_A") (pintype "passive"))
      (node (ref "LED121") (pin "A") (pinfunction "A_A") (pintype "passive"))
      (node (ref "LED122") (pin "C") (pinfunction "C_C") (pintype "passive"))
      (node (ref "LED147") (pin "A") (pinfunction "A_A") (pintype "passive"))
      (node (ref "LED148") (pin "C") (pinfunction "C_C") (pintype "passive"))
      (node (ref "LED151") (pin "A") (pinfunction "A_A") (pintype "passive"))
      (node (ref "LED152") (pin "C") (pinfunction "C_C") (pintype "passive"))
      (node (ref "LED2") (pin "C") (pinfunction "C_C") (pintype "passive"))
      (node (ref "LED27") (pin "A") (pinfunction "A_A") (pintype "passive"))
      (node (ref "LED28") (pin "C") (pinfunction "C_C") (pintype "passive"))
      (node (ref "LED31") (pin "A") (pinfunction "A_A") (pintype "passive"))
      (node (ref "LED32") (pin "C") (pinfunction "C_C") (pintype "passive"))
      (node (ref "LED62") (pin "C") (pinfunction "C_C") (pintype "passive"))
      (node (ref "LED63") (pin "A") (pinfunction "A_A") (pintype "passive"))
      (node (ref "LED88") (pin "C") (pinfunction "C_C") (pintype "passive"))
      (node (ref "LED89") (pin "A") (pinfunction "A_A") (pintype "passive"))
      (node (ref "LED92") (pin "C") (pinfunction "C_C") (pintype "passive"))
      (node (ref "LED93") (pin "A") (pinfunction "A_A") (pintype "passive"))
    )
    (net (code "5") (name "/5") (class "Default")
      (node (ref "LED123") (pin "A") (pinfunction "A_A") (pintype "passive"))
      (node (ref "LED124") (pin "C") (pinfunction "C_C") (pintype "passive"))
      (node (ref "LED149") (pin "A") (pinfunction "A_A") (pintype "passive"))
      (node (ref "LED150") (pin "C") (pinfunction "C_C") (pintype "passive"))
      (node (ref "LED153") (pin "A") (pinfunction "A_A") (pintype "passive"))
      (node (ref "LED154") (pin "C") (pinfunction "C_C") (pintype "passive"))
      (node (ref "LED29") (pin "A") (pinfunction "A_A") (pintype "passive"))
      (node (ref "LED3") (pin "A") (pinfunction "A_A") (pintype "passive"))
      (node (ref "LED30") (pin "C") (pinfunction "C_C") (pintype "passive"))
      (node (ref "LED33") (pin "A") (pinfunction "A_A") (pintype "passive"))
      (node (ref "LED34") (pin "C") (pinfunction "C_C") (pintype "passive"))
      (node (ref "LED4") (pin "C") (pinfunction "C_C") (pintype "passive"))
      (node (ref "LED64") (pin "C") (pinfunction "C_C") (pintype "passive"))
      (node (ref "LED65") (pin "A") (pinfunction "A_A") (pintype "passive"))
      (node (ref "LED90") (pin "C") (pinfunction "C_C") (pintype "passive"))
      (node (ref "LED91") (pin "A") (pinfunction "A_A") (pintype "passive"))
      (node (ref "LED94") (pin "C") (pinfunction "C_C") (pintype "passive"))
      (node (ref "LED95") (pin "A") (pinfunction "A_A") (pintype "passive"))
    )
    (net (code "6") (name "/6") (class "Default")
      (node (ref "LED125") (pin "A") (pinfunction "A_A") (pintype "passive"))
      (node (ref "LED126") (pin "C") (pinfunction "C_C") (pintype "passive"))
      (node (ref "LED155") (pin "A") (pinfunction "A_A") (pintype "passive"))
      (node (ref "LED156") (pin "C") (pinfunction "C_C") (pintype "passive"))
      (node (ref "LED35") (pin "A") (pinfunction "A_A") (pintype "passive"))
      (node (ref "LED36") (pin "C") (pinfunction "C_C") (pintype "passive"))
      (node (ref "LED41") (pin "C") (pinfunction "C_C") (pintype "passive"))
      (node (ref "LED42") (pin "A") (pinfunction "A_A") (pintype "passive"))
      (node (ref "LED43") (pin "C") (pinfunction "C_C") (pintype "passive"))
      (node (ref "LED44") (pin "A") (pinfunction "A_A") (pintype "passive"))
      (node (ref "LED45") (pin "C") (pinfunction "C_C") (pintype "passive"))
      (node (ref "LED46") (pin "A") (pinfunction "A_A") (pintype "passive"))
      (node (ref "LED47") (pin "C") (pinfunction "C_C") (pintype "passive"))
      (node (ref "LED48") (pin "A") (pinfunction "A_A") (pintype "passive"))
      (node (ref "LED49") (pin "C") (pinfunction "C_C") (pintype "passive"))
      (node (ref "LED5") (pin "A") (pinfunction "A_A") (pintype "passive"))
      (node (ref "LED50") (pin "A") (pinfunction "A_A") (pintype "passive"))
      (node (ref "LED6") (pin "C") (pinfunction "C_C") (pintype "passive"))
      (node (ref "LED66") (pin "C") (pinfunction "C_C") (pintype "passive"))
      (node (ref "LED67") (pin "A") (pinfunction "A_A") (pintype "passive"))
      (node (ref "LED96") (pin "C") (pinfunction "C_C") (pintype "passive"))
      (node (ref "LED97") (pin "A") (pinfunction "A_A") (pintype "passive"))
    )
    (net (code "7") (name "/7") (class "Default")
      (node (ref "LED102") (pin "A") (pinfunction "A_A") (pintype "passive"))
      (node (ref "LED103") (pin "C") (pinfunction "C_C") (pintype "passive"))
      (node (ref "LED104") (pin "A") (pinfunction "A_A") (pintype "passive"))
      (node (ref "LED105") (pin "C") (pinfunction "C_C") (pintype "passive"))
      (node (ref "LED106") (pin "A") (pinfunction "A_A") (pintype "passive"))
      (node (ref "LED107") (pin "C") (pinfunction "C_C") (pintype "passive"))
      (node (ref "LED108") (pin "A") (pinfunction "A_A") (pintype "passive"))
      (node (ref "LED109") (pin "C") (pinfunction "C_C") (pintype "passive"))
      (node (ref "LED110") (pin "A") (pinfunction "A_A") (pintype "passive"))
      (node (ref "LED111") (pin "C") (pinfunction "C_C") (pintype "passive"))
      (node (ref "LED127") (pin "A") (pinfunction "A_A") (pintype "passive"))
      (node (ref "LED128") (pin "C") (pinfunction "C_C") (pintype "passive"))
      (node (ref "LED157") (pin "A") (pinfunction "A_A") (pintype "passive"))
      (node (ref "LED158") (pin "C") (pinfunction "C_C") (pintype "passive"))
      (node (ref "LED37") (pin "A") (pinfunction "A_A") (pintype "passive"))
      (node (ref "LED38") (pin "C") (pinfunction "C_C") (pintype "passive"))
      (node (ref "LED68") (pin "C") (pinfunction "C_C") (pintype "passive"))
      (node (ref "LED69") (pin "A") (pinfunction "A_A") (pintype "passive"))
      (node (ref "LED7") (pin "A") (pinfunction "A_A") (pintype "passive"))
      (node (ref "LED8") (pin "C") (pinfunction "C_C") (pintype "passive"))
      (node (ref "LED98") (pin "C") (pinfunction "C_C") (pintype "passive"))
      (node (ref "LED99") (pin "A") (pinfunction "A_A") (pintype "passive"))
    )
    (net (code "8") (name "/8") (class "Default")
      (node (ref "LED10") (pin "C") (pinfunction "C_C") (pintype "passive"))
      (node (ref "LED100") (pin "C") (pinfunction "C_C") (pintype "passive"))
      (node (ref "LED101") (pin "A") (pinfunction "A_A") (pintype "passive"))
      (node (ref "LED129") (pin "A") (pinfunction "A_A") (pintype "passive"))
      (node (ref "LED130") (pin "C") (pinfunction "C_C") (pintype "passive"))
      (node (ref "LED159") (pin "A") (pinfunction "A_A") (pintype "passive"))
      (node (ref "LED160") (pin "C") (pinfunction "C_C") (pintype "passive"))
      (node (ref "LED161") (pin "C") (pinfunction "C_C") (pintype "passive"))
      (node (ref "LED162") (pin "A") (pinfunction "A_A") (pintype "passive"))
      (node (ref "LED163") (pin "C") (pinfunction "C_C") (pintype "passive"))
      (node (ref "LED164") (pin "A") (pinfunction "A_A") (pintype "passive"))
      (node (ref "LED165") (pin "C") (pinfunction "C_C") (pintype "passive"))
      (node (ref "LED166") (pin "A") (pinfunction "A_A") (pintype "passive"))
      (node (ref "LED167") (pin "C") (pinfunction "C_C") (pintype "passive"))
      (node (ref "LED168") (pin "A") (pinfunction "A_A") (pintype "passive"))
      (node (ref "LED169") (pin "C") (pinfunction "C_C") (pintype "passive"))
      (node (ref "LED170") (pin "A") (pinfunction "A_A") (pintype "passive"))
      (node (ref "LED39") (pin "A") (pinfunction "A_A") (pintype "passive"))
      (node (ref "LED40") (pin "C") (pinfunction "C_C") (pintype "passive"))
      (node (ref "LED70") (pin "C") (pinfunction "C_C") (pintype "passive"))
      (node (ref "LED71") (pin "A") (pinfunction "A_A") (pintype "passive"))
      (node (ref "LED9") (pin "A") (pinfunction "A_A") (pintype "passive"))
    )
    (net (code "9") (name "/9") (class "Default")
      (node (ref "LED11") (pin "A") (pinfunction "A_A") (pintype "passive"))
      (node (ref "LED112") (pin "C") (pinfunction "C_C") (pintype "passive"))
      (node (ref "LED113") (pin "A") (pinfunction "A_A") (pintype "passive"))
      (node (ref "LED12") (pin "C") (pinfunction "C_C") (pintype "passive"))
      (node (ref "LED131") (pin "A") (pinfunction "A_A") (pintype "passive"))
      (node (ref "LED132") (pin "C") (pinfunction "C_C") (pintype "passive"))
      (node (ref "LED171") (pin "A") (pinfunction "A_A") (pintype "passive"))
      (node (ref "LED172") (pin "C") (pinfunction "C_C") (pintype "passive"))
      (node (ref "LED31") (pin "C") (pinfunction "C_C") (pintype "passive"))
      (node (ref "LED32") (pin "A") (pinfunction "A_A") (pintype "passive"))
      (node (ref "LED33") (pin "C") (pinfunction "C_C") (pintype "passive"))
      (node (ref "LED34") (pin "A") (pinfunction "A_A") (pintype "passive"))
      (node (ref "LED35") (pin "C") (pinfunction "C_C") (pintype "passive"))
      (node (ref "LED36") (pin "A") (pinfunction "A_A") (pintype "passive"))
      (node (ref "LED37") (pin "C") (pinfunction "C_C") (pintype "passive"))
      (node (ref "LED38") (pin "A") (pinfunction "A_A") (pintype "passive"))
      (node (ref "LED39") (pin "C") (pinfunction "C_C") (pintype "passive"))
      (node (ref "LED40") (pin "A") (pinfunction "A_A") (pintype "passive"))
      (node (ref "LED51") (pin "A") (pinfunction "A_A") (pintype "passive"))
      (node (ref "LED52") (pin "C") (pinfunction "C_C") (pintype "passive"))
      (node (ref "LED72") (pin "C") (pinfunction "C_C") (pintype "passive"))
      (node (ref "LED73") (pin "A") (pinfunction "A_A") (pintype "passive"))
    )
    (net (code "10") (name "/10") (class "Default")
      (node (ref "LED100") (pin "A") (pinfunction "A_A") (pintype "passive"))
      (node (ref "LED101") (pin "C") (pinfunction "C_C") (pintype "passive"))
      (node (ref "LED114") (pin "C") (pinfunction "C_C") (pintype "passive"))
      (node (ref "LED115") (pin "A") (pinfunction "A_A") (pintype "passive"))
      (node (ref "LED13") (pin "A") (pinfunction "A_A") (pintype "passive"))
      (node (ref "LED133") (pin "A") (pinfunction "A_A") (pintype "passive"))
      (node (ref "LED134") (pin "C") (pinfunction "C_C") (pintype "passive"))
      (node (ref "LED14") (pin "C") (pinfunction "C_C") (pintype "passive"))
      (node (ref "LED173") (pin "A") (pinfunction "A_A") (pintype "passive"))
      (node (ref "LED174") (pin "C") (pinfunction "C_C") (pintype "passive"))
      (node (ref "LED53") (pin "A") (pinfunction "A_A") (pintype "passive"))
      (node (ref "LED54") (pin "C") (pinfunction "C_C") (pintype "passive"))
      (node (ref "LED74") (pin "C") (pinfunction "C_C") (pintype "passive"))
      (node (ref "LED75") (pin "A") (pinfunction "A_A") (pintype "passive"))
      (node (ref "LED92") (pin "A") (pinfunction "A_A") (pintype "passive"))
      (node (ref "LED93") (pin "C") (pinfunction "C_C") (pintype "passive"))
      (node (ref "LED94") (pin "A") (pinfunction "A_A") (pintype "passive"))
      (node (ref "LED95") (pin "C") (pinfunction "C_C") (pintype "passive"))
      (node (ref "LED96") (pin "A") (pinfunction "A_A") (pintype "passive"))
      (node (ref "LED97") (pin "C") (pinfunction "C_C") (pintype "passive"))
      (node (ref "LED98") (pin "A") (pinfunction "A_A") (pintype "passive"))
      (node (ref "LED99") (pin "C") (pinfunction "C_C") (pintype "passive"))
    )
    (net (code "11") (name "/11") (class "Default")
      (node (ref "LED116") (pin "C") (pinfunction "C_C") (pintype "passive"))
      (node (ref "LED117") (pin "A") (pinfunction "A_A") (pintype "passive"))
      (node (ref "LED135") (pin "A") (pinfunction "A_A") (pintype "passive"))
      (node (ref "LED136") (pin "C") (pinfunction "C_C") (pintype "passive"))
      (node (ref "LED15") (pin "A") (pinfunction "A_A") (pintype "passive"))
      (node (ref "LED151") (pin "C") (pinfunction "C_C") (pintype "passive"))
      (node (ref "LED152") (pin "A") (pinfunction "A_A") (pintype "passive"))
      (node (ref "LED153") (pin "C") (pinfunction "C_C") (pintype "passive"))
      (node (ref "LED154") (pin "A") (pinfunction "A_A") (pintype "passive"))
      (node (ref "LED155") (pin "C") (pinfunction "C_C") (pintype "passive"))
      (node (ref "LED156") (pin "A") (pinfunction "A_A") (pintype "passive"))
      (node (ref "LED157") (pin "C") (pinfunction "C_C") (pintype "passive"))
      (node (ref "LED158") (pin "A") (pinfunction "A_A") (pintype "passive"))
      (node (ref "LED159") (pin "C") (pinfunction "C_C") (pintype "passive"))
      (node (ref "LED16") (pin "C") (pinfunction "C_C") (pintype "passive"))
      (node (ref "LED160") (pin "A") (pinfunction "A_A") (pintype "passive"))
      (node (ref "LED175") (pin "A") (pinfunction "A_A") (pintype "passive"))
      (node (ref "LED176") (pin "C") (pinfunction "C_C") (pintype "passive"))
      (node (ref "LED55") (pin "A") (pinfunction "A_A") (pintype "passive"))
      (node (ref "LED56") (pin "C") (pinfunction "C_C") (pintype "passive"))
      (node (ref "LED76") (pin "C") (pinfunction "C_C") (pintype "passive"))
      (node (ref "LED77") (pin "A") (pinfunction "A_A") (pintype "passive"))
    )
    (net (code "12") (name "/12") (class "Default")
      (node (ref "LED102") (pin "C") (pinfunction "C_C") (pintype "passive"))
      (node (ref "LED103") (pin "A") (pinfunction "A_A") (pintype "passive"))
      (node (ref "LED118") (pin "C") (pinfunction "C_C") (pintype "passive"))
      (node (ref "LED119") (pin "A") (pinfunction "A_A") (pintype "passive"))
      (node (ref "LED137") (pin "A") (pinfunction "A_A") (pintype "passive"))
      (node (ref "LED138") (pin "C") (pinfunction "C_C") (pintype "passive"))
      (node (ref "LED161") (pin "A") (pinfunction "A_A") (pintype "passive"))
      (node (ref "LED162") (pin "C") (pinfunction "C_C") (pintype "passive"))
      (node (ref "LED17") (pin "A") (pinfunction "A_A") (pintype "passive"))
      (node (ref "LED177") (pin "A") (pinfunction "A_A") (pintype "passive"))
      (node (ref "LED178") (pin "C") (pinfunction "C_C") (pintype "passive"))
      (node (ref "LED18") (pin "C") (pinfunction "C_C") (pintype "passive"))
      (node (ref "LED41") (pin "A") (pinfunction "A_A") (pintype "passive"))
      (node (ref "LED42") (pin "C") (pinfunction "C_C") (pintype "passive"))
      (node (ref "LED57") (pin "A") (pinfunction "A_A") (pintype "passive"))
      (node (ref "LED58") (pin "C") (pinfunction "C_C") (pintype "passive"))
      (node (ref "LED78") (pin "C") (pinfunction "C_C") (pintype "passive"))
      (node (ref "LED79") (pin "A") (pinfunction "A_A") (pintype "passive"))
    )
    (net (code "13") (name "/13") (class "Default")
      (node (ref "LED104") (pin "C") (pinfunction "C_C") (pintype "passive"))
      (node (ref "LED105") (pin "A") (pinfunction "A_A") (pintype "passive"))
      (node (ref "LED120") (pin "C") (pinfunction "C_C") (pintype "passive"))
      (node (ref "LED139") (pin "A") (pinfunction "A_A") (pintype "passive"))
      (node (ref "LED140") (pin "C") (pinfunction "C_C") (pintype "passive"))
      (node (ref "LED163") (pin "A") (pinfunction "A_A") (pintype "passive"))
      (node (ref "LED164") (pin "C") (pinfunction "C_C") (pintype "passive"))
      (node (ref "LED179") (pin "A") (pinfunction "A_A") (pintype "passive"))
      (node (ref "LED180") (pin "C") (pinfunction "C_C") (pintype "passive"))
      (node (ref "LED19") (pin "A") (pinfunction "A_A") (pintype "passive"))
      (node (ref "LED20") (pin "C") (pinfunction "C_C") (pintype "passive"))
      (node (ref "LED43") (pin "A") (pinfunction "A_A") (pintype "passive"))
      (node (ref "LED44") (pin "C") (pinfunction "C_C") (pintype "passive"))
      (node (ref "LED59") (pin "A") (pinfunction "A_A") (pintype "passive"))
      (node (ref "LED60") (pin "C") (pinfunction "C_C") (pintype "passive"))
      (node (ref "LED61") (pin "A") (pinfunction "A_A") (pintype "passive"))
      (node (ref "LED80") (pin "C") (pinfunction "C_C") (pintype "passive"))
      (node (ref "LED81") (pin "A") (pinfunction "A_A") (pintype "passive"))
    )
    (net (code "14") (name "/14") (class "Default")
      (node (ref "LED106") (pin "C") (pinfunction "C_C") (pintype "passive"))
      (node (ref "LED107") (pin "A") (pinfunction "A_A") (pintype "passive"))
      (node (ref "LED165") (pin "A") (pinfunction "A_A") (pintype "passive"))
      (node (ref "LED166") (pin "C") (pinfunction "C_C") (pintype "passive"))
      (node (ref "LED21") (pin "C") (pinfunction "C_C") (pintype "passive"))
      (node (ref "LED22") (pin "A") (pinfunction "A_A") (pintype "passive"))
      (node (ref "LED23") (pin "C") (pinfunction "C_C") (pintype "passive"))
      (node (ref "LED24") (pin "A") (pinfunction "A_A") (pintype "passive"))
      (node (ref "LED25") (pin "C") (pinfunction "C_C") (pintype "passive"))
      (node (ref "LED26") (pin "A") (pinfunction "A_A") (pintype "passive"))
      (node (ref "LED27") (pin "C") (pinfunction "C_C") (pintype "passive"))
      (node (ref "LED28") (pin "A") (pinfunction "A_A") (pintype "passive"))
      (node (ref "LED29") (pin "C") (pinfunction "C_C") (pintype "passive"))
      (node (ref "LED30") (pin "A") (pinfunction "A_A") (pintype "passive"))
      (node (ref "LED45") (pin "A") (pinfunction "A_A") (pintype "passive"))
      (node (ref "LED46") (pin "C") (pinfunction "C_C") (pintype "passive"))
      (node (ref "LED51") (pin "C") (pinfunction "C_C") (pintype "passive"))
      (node (ref "LED52") (pin "A") (pinfunction "A_A") (pintype "passive"))
      (node (ref "LED53") (pin "C") (pinfunction "C_C") (pintype "passive"))
      (node (ref "LED54") (pin "A") (pinfunction "A_A") (pintype "passive"))
      (node (ref "LED55") (pin "C") (pinfunction "C_C") (pintype "passive"))
      (node (ref "LED56") (pin "A") (pinfunction "A_A") (pintype "passive"))
      (node (ref "LED57") (pin "C") (pinfunction "C_C") (pintype "passive"))
      (node (ref "LED58") (pin "A") (pinfunction "A_A") (pintype "passive"))
      (node (ref "LED59") (pin "C") (pinfunction "C_C") (pintype "passive"))
      (node (ref "LED60") (pin "A") (pinfunction "A_A") (pintype "passive"))
    )
    (net (code "15") (name "/15") (class "Default")
      (node (ref "LED108") (pin "C") (pinfunction "C_C") (pintype "passive"))
      (node (ref "LED109") (pin "A") (pinfunction "A_A") (pintype "passive"))
      (node (ref "LED112") (pin "A") (pinfunction "A_A") (pintype "passive"))
      (node (ref "LED113") (pin "C") (pinfunction "C_C") (pintype "passive"))
      (node (ref "LED114") (pin "A") (pinfunction "A_A") (pintype "passive"))
      (node (ref "LED115") (pin "C") (pinfunction "C_C") (pintype "passive"))
      (node (ref "LED116") (pin "A") (pinfunction "A_A") (pintype "passive"))
      (node (ref "LED117") (pin "C") (pinfunction "C_C") (pintype "passive"))
      (node (ref "LED118") (pin "A") (pinfunction "A_A") (pintype "passive"))
      (node (ref "LED119") (pin "C") (pinfunction "C_C") (pintype "passive"))
      (node (ref "LED120") (pin "A") (pinfunction "A_A") (pintype "passive"))
      (node (ref "LED167") (pin "A") (pinfunction "A_A") (pintype "passive"))
      (node (ref "LED168") (pin "C") (pinfunction "C_C") (pintype "passive"))
      (node (ref "LED47") (pin "A") (pinfunction "A_A") (pintype "passive"))
      (node (ref "LED48") (pin "C") (pinfunction "C_C") (pintype "passive"))
      (node (ref "LED61") (pin "C") (pinfunction "C_C") (pintype "passive"))
      (node (ref "LED82") (pin "A") (pinfunction "A_A") (pintype "passive"))
      (node (ref "LED83") (pin "C") (pinfunction "C_C") (pintype "passive"))
      (node (ref "LED84") (pin "A") (pinfunction "A_A") (pintype "passive"))
      (node (ref "LED85") (pin "C") (pinfunction "C_C") (pintype "passive"))
      (node (ref "LED86") (pin "A") (pinfunction "A_A") (pintype "passive"))
      (node (ref "LED87") (pin "C") (pinfunction "C_C") (pintype "passive"))
      (node (ref "LED88") (pin "A") (pinfunction "A_A") (pintype "passive"))
      (node (ref "LED89") (pin "C") (pinfunction "C_C") (pintype "passive"))
      (node (ref "LED90") (pin "A") (pinfunction "A_A") (pintype "passive"))
      (node (ref "LED91") (pin "C") (pinfunction "C_C") (pintype "passive"))
    )
    (net (code "16") (name "/16") (class "Default")
      (node (ref "LED110") (pin "C") (pinfunction "C_C") (pintype "passive"))
      (node (ref "LED111") (pin "A") (pinfunction "A_A") (pintype "passive"))
      (node (ref "LED141") (pin "C") (pinfunction "C_C") (pintype "passive"))
      (node (ref "LED142") (pin "A") (pinfunction "A_A") (pintype "passive"))
      (node (ref "LED143") (pin "C") (pinfunction "C_C") (pintype "passive"))
      (node (ref "LED144") (pin "A") (pinfunction "A_A") (pintype "passive"))
      (node (ref "LED145") (pin "C") (pinfunction "C_C") (pintype "passive"))
      (node (ref "LED146") (pin "A") (pinfunction "A_A") (pintype "passive"))
      (node (ref "LED147") (pin "C") (pinfunction "C_C") (pintype "passive"))
      (node (ref "LED148") (pin "A") (pinfunction "A_A") (pintype "passive"))
      (node (ref "LED149") (pin "C") (pinfunction "C_C") (pintype "passive"))
      (node (ref "LED150") (pin "A") (pinfunction "A_A") (pintype "passive"))
      (node (ref "LED169") (pin "A") (pinfunction "A_A") (pintype "passive"))
      (node (ref "LED170") (pin "C") (pinfunction "C_C") (pintype "passive"))
      (node (ref "LED171") (pin "C") (pinfunction "C_C") (pintype "passive"))
      (node (ref "LED172") (pin "A") (pinfunction "A_A") (pintype "passive"))
      (node (ref "LED173") (pin "C") (pinfunction "C_C") (pintype "passive"))
      (node (ref "LED174") (pin "A") (pinfunction "A_A") (pintype "passive"))
      (node (ref "LED175") (pin "C") (pinfunction "C_C") (pintype "passive"))
      (node (ref "LED176") (pin "A") (pinfunction "A_A") (pintype "passive"))
      (node (ref "LED177") (pin "C") (pinfunction "C_C") (pintype "passive"))
      (node (ref "LED178") (pin "A") (pinfunction "A_A") (pintype "passive"))
      (node (ref "LED179") (pin "C") (pinfunction "C_C") (pintype "passive"))
      (node (ref "LED180") (pin "A") (pinfunction "A_A") (pintype "passive"))
      (node (ref "LED49") (pin "A") (pinfunction "A_A") (pintype "passive"))
      (node (ref "LED50") (pin "C") (pinfunction "C_C") (pintype "passive"))
    )
  )
)
